# main_power.net
KiCad netlist of a schematic drawn in EAGLE
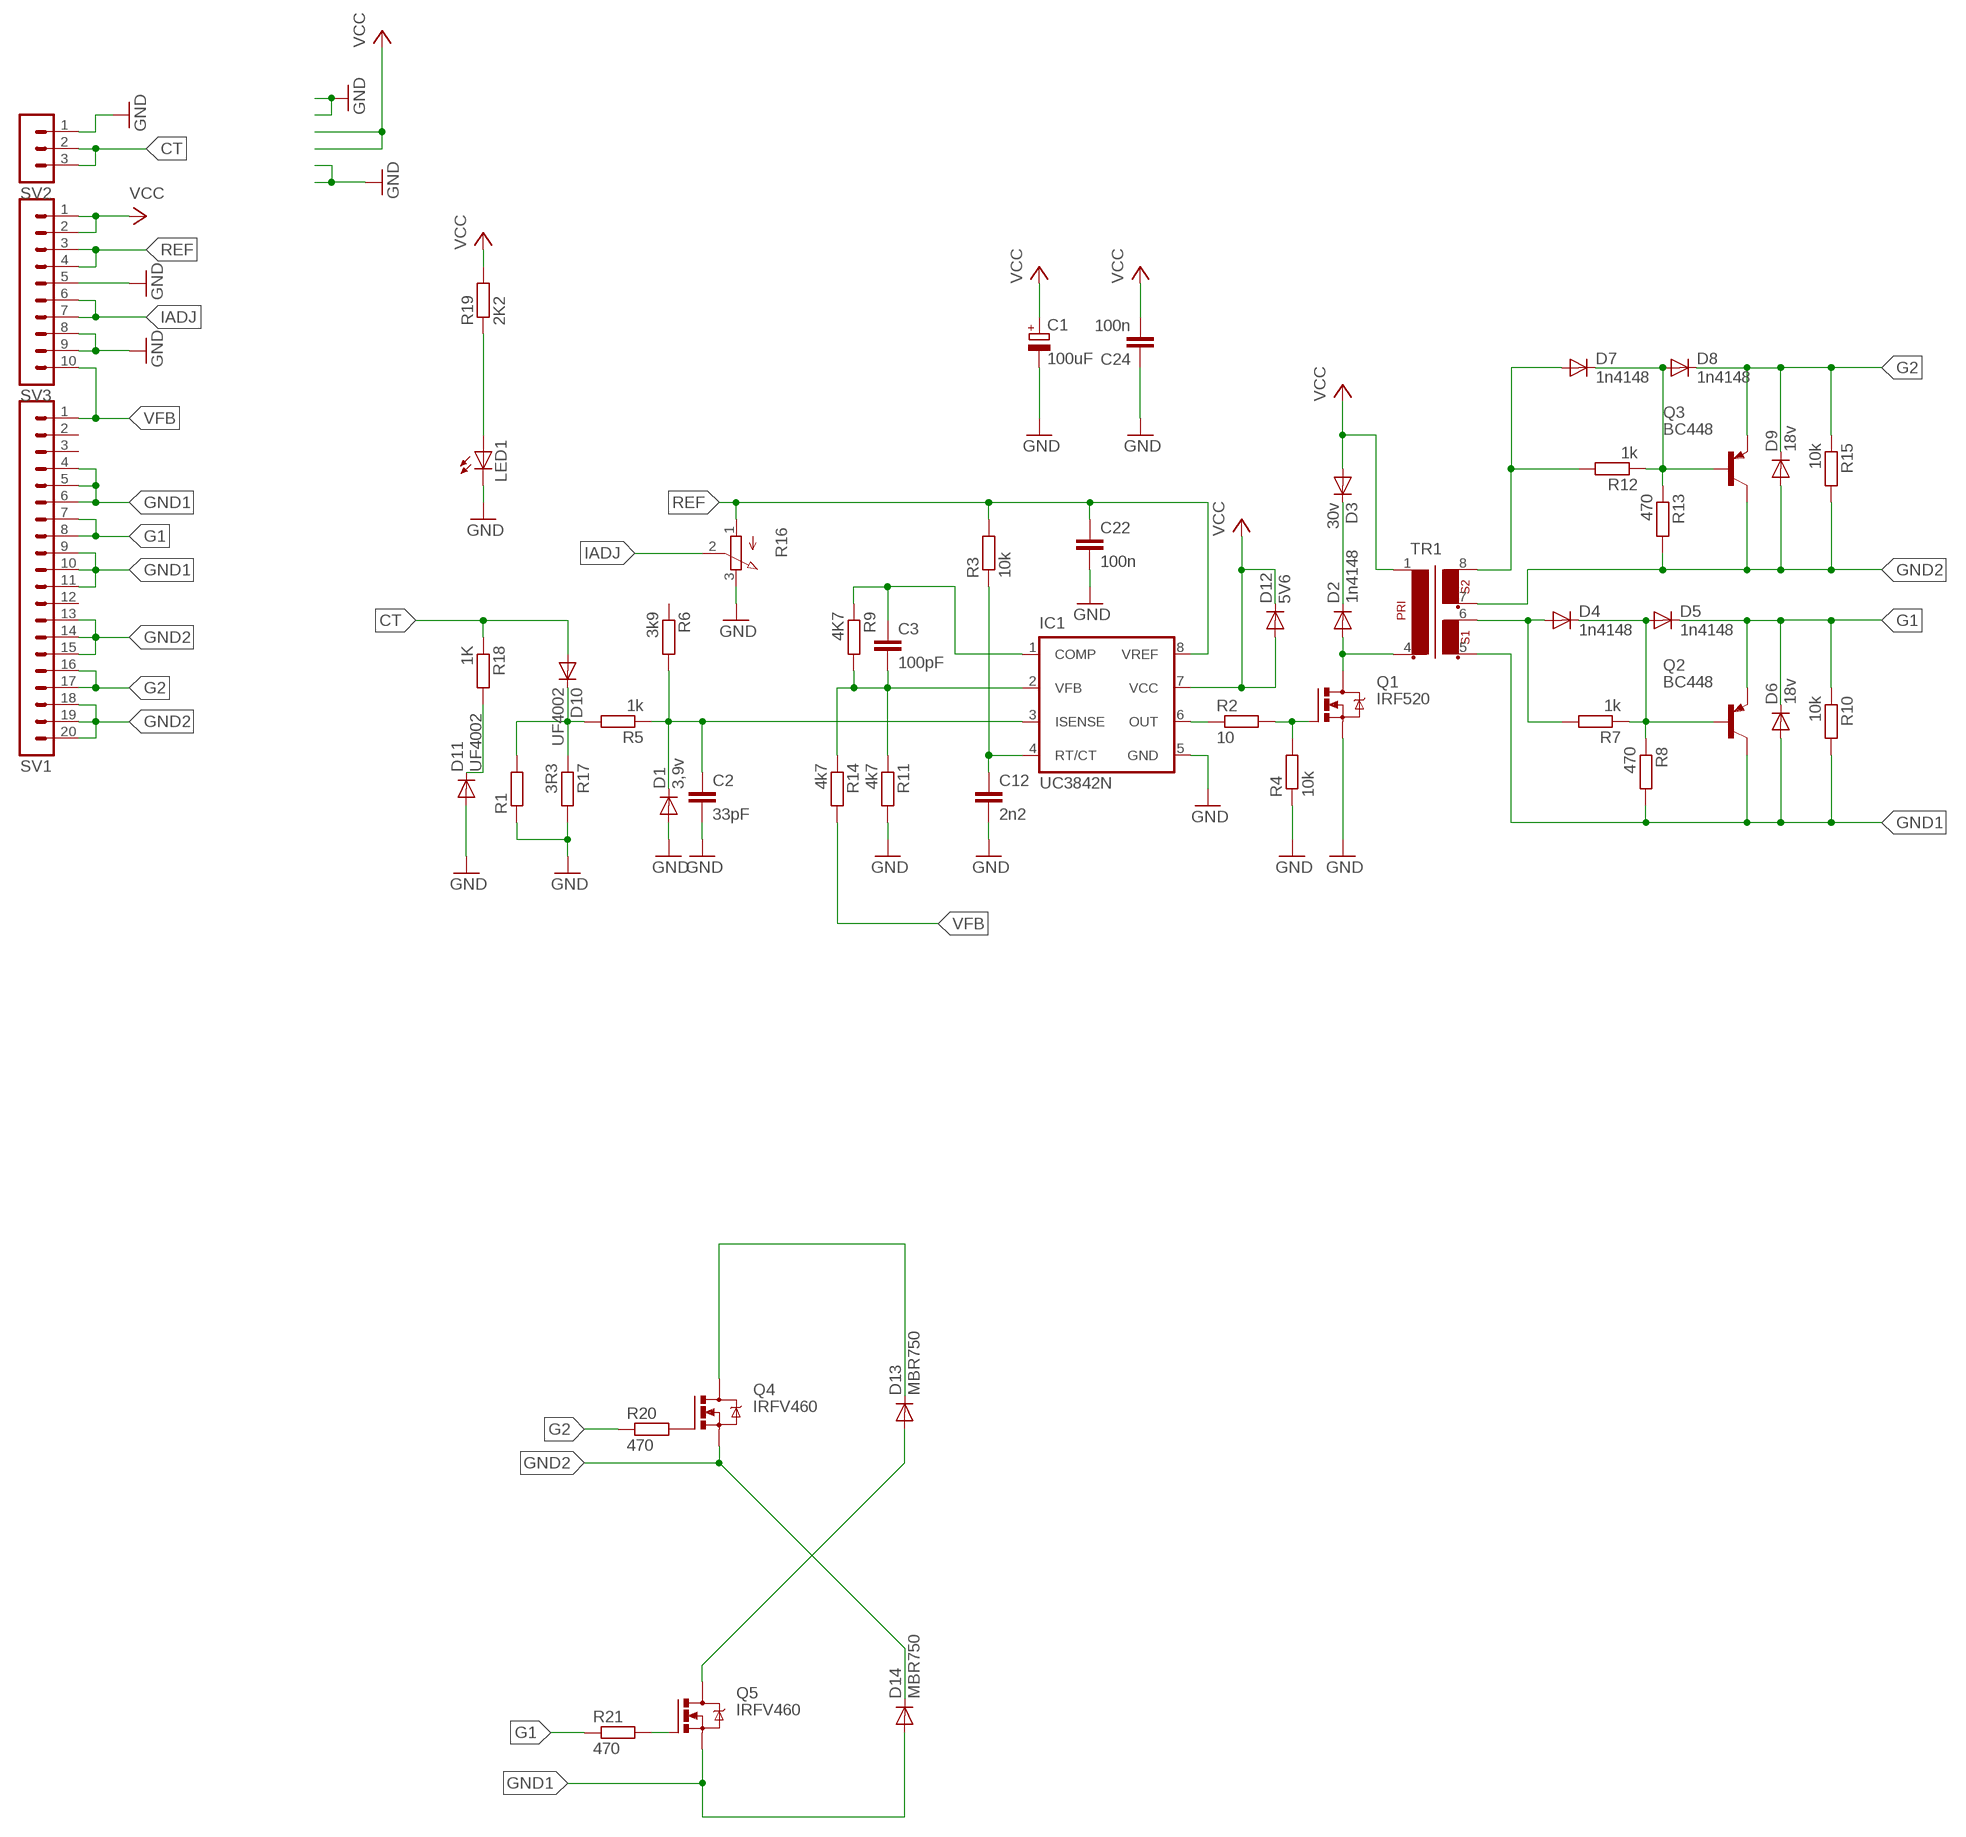
[diagram p0: schematic, sheet 1]

(export (version "E")
  (design (tool "Eeschema 10.0.6"))
  (components
    (comp (ref "C1")
      (value "100uF")
      (footprint "eagle-import:E5-6")
      (libsource (lib "eagle-import") (part "CPOL-EUE5-6"))
    )
    (comp (ref "C2")
      (value "33pF")
      (footprint "eagle-import:C050-025X075")
      (libsource (lib "eagle-import") (part "C-EU050-025X075"))
    )
    (comp (ref "C3")
      (value "100pF")
      (footprint "eagle-import:C050-025X075")
      (libsource (lib "eagle-import") (part "C-EU050-025X075"))
    )
    (comp (ref "C12")
      (value "2n2")
      (footprint "eagle-import:C050-025X075")
      (libsource (lib "eagle-import") (part "C-EU050-025X075"))
    )
    (comp (ref "C22")
      (value "100n")
      (footprint "eagle-import:C050-025X075")
      (libsource (lib "eagle-import") (part "C-EU050-025X075"))
    )
    (comp (ref "C24")
      (value "100n")
      (footprint "eagle-import:C050-025X075")
      (libsource (lib "eagle-import") (part "C-EU050-025X075"))
    )
    (comp (ref "D1")
      (value "3,9v")
      (footprint "eagle-import:DO35-10")
      (libsource (lib "eagle-import") (part "1N4446"))
    )
    (comp (ref "D2")
      (value "1n4148")
      (footprint "eagle-import:DO35-10")
      (libsource (lib "eagle-import") (part "1N4446"))
    )
    (comp (ref "D3")
      (value "30v")
      (footprint "eagle-import:DO35-10")
      (libsource (lib "eagle-import") (part "1N4446"))
    )
    (comp (ref "D4")
      (value "1n4148")
      (footprint "eagle-import:DO35-10")
      (libsource (lib "eagle-import") (part "1N4446"))
    )
    (comp (ref "D5")
      (value "1n4148")
      (footprint "eagle-import:DO35-10")
      (libsource (lib "eagle-import") (part "1N4446"))
    )
    (comp (ref "D6")
      (value "18v")
      (footprint "eagle-import:DO35-10")
      (libsource (lib "eagle-import") (part "1N4446"))
    )
    (comp (ref "D7")
      (value "1n4148")
      (footprint "eagle-import:DO35-10")
      (libsource (lib "eagle-import") (part "1N4446"))
    )
    (comp (ref "D8")
      (value "1n4148")
      (footprint "eagle-import:DO35-10")
      (libsource (lib "eagle-import") (part "1N4446"))
    )
    (comp (ref "D9")
      (value "18v")
      (footprint "eagle-import:DO35-10")
      (libsource (lib "eagle-import") (part "1N4446"))
    )
    (comp (ref "D10")
      (value "UF4002")
      (footprint "eagle-import:DO35-10")
      (libsource (lib "eagle-import") (part "1N4446"))
    )
    (comp (ref "D11")
      (value "UF4002")
      (footprint "eagle-import:DO35-10")
      (libsource (lib "eagle-import") (part "1N4446"))
    )
    (comp (ref "D12")
      (value "5V6")
      (footprint "eagle-import:DO35-10")
      (libsource (lib "eagle-import") (part "1N4446"))
    )
    (comp (ref "D13")
      (value "MBR750")
      (footprint "eagle-import:TO220AC")
      (libsource (lib "eagle-import") (part "MBR750"))
    )
    (comp (ref "D14")
      (value "MBR750")
      (footprint "eagle-import:TO220AC")
      (libsource (lib "eagle-import") (part "MBR750"))
    )
    (comp (ref "IC1")
      (value "UC3842N")
      (footprint "eagle-import:DIL08")
      (libsource (lib "eagle-import") (part "UC384N2"))
    )
    (comp (ref "LED1")
      (value "LED5MM")
      (footprint "eagle-import:LED5MM")
      (libsource (lib "eagle-import") (part "LED5MM"))
    )
    (comp (ref "Q1")
      (value "IRF520")
      (footprint "eagle-import:TO220BV")
      (libsource (lib "eagle-import") (part "IRF520"))
    )
    (comp (ref "Q2")
      (value "BC448")
      (footprint "eagle-import:TO92-EBC")
      (libsource (lib "eagle-import") (part "BC448"))
    )
    (comp (ref "Q3")
      (value "BC448")
      (footprint "eagle-import:TO92-EBC")
      (libsource (lib "eagle-import") (part "BC448"))
    )
    (comp (ref "Q4")
      (value "IRFV460")
      (footprint "eagle-import:TO258AA")
      (libsource (lib "eagle-import") (part "IRFV460"))
    )
    (comp (ref "Q5")
      (value "IRFV460")
      (footprint "eagle-import:TO258AA")
      (libsource (lib "eagle-import") (part "IRFV460"))
    )
    (comp (ref "R1")
      (value "R-EU_0411/12")
      (footprint "eagle-import:0411_12")
      (libsource (lib "eagle-import") (part "R-EU_0411/12"))
    )
    (comp (ref "R2")
      (value "10")
      (footprint "eagle-import:0207_10")
      (libsource (lib "eagle-import") (part "R-EU_0207/10"))
    )
    (comp (ref "R3")
      (value "10k")
      (footprint "eagle-import:0207_10")
      (libsource (lib "eagle-import") (part "R-EU_0207/10"))
    )
    (comp (ref "R4")
      (value "10k")
      (footprint "eagle-import:0207_10")
      (libsource (lib "eagle-import") (part "R-EU_0207/10"))
    )
    (comp (ref "R5")
      (value "1k")
      (footprint "eagle-import:0207_10")
      (libsource (lib "eagle-import") (part "R-EU_0207/10"))
    )
    (comp (ref "R6")
      (value "3k9")
      (footprint "eagle-import:0207_10")
      (libsource (lib "eagle-import") (part "R-EU_0207/10"))
    )
    (comp (ref "R7")
      (value "1k")
      (footprint "eagle-import:0207_10")
      (libsource (lib "eagle-import") (part "R-EU_0207/10"))
    )
    (comp (ref "R8")
      (value "470")
      (footprint "eagle-import:0207_10")
      (libsource (lib "eagle-import") (part "R-EU_0207/10"))
    )
    (comp (ref "R9")
      (value "4K7")
      (footprint "eagle-import:0207_10")
      (libsource (lib "eagle-import") (part "R-EU_0207/10"))
    )
    (comp (ref "R10")
      (value "10k")
      (footprint "eagle-import:0207_10")
      (libsource (lib "eagle-import") (part "R-EU_0207/10"))
    )
    (comp (ref "R11")
      (value "4k7")
      (footprint "eagle-import:0207_10")
      (libsource (lib "eagle-import") (part "R-EU_0207/10"))
    )
    (comp (ref "R12")
      (value "1k")
      (footprint "eagle-import:0207_10")
      (libsource (lib "eagle-import") (part "R-EU_0207/10"))
    )
    (comp (ref "R13")
      (value "470")
      (footprint "eagle-import:0207_10")
      (libsource (lib "eagle-import") (part "R-EU_0207/10"))
    )
    (comp (ref "R14")
      (value "4k7")
      (footprint "eagle-import:0207_10")
      (libsource (lib "eagle-import") (part "R-EU_0207/10"))
    )
    (comp (ref "R15")
      (value "10k")
      (footprint "eagle-import:0207_10")
      (libsource (lib "eagle-import") (part "R-EU_0207/10"))
    )
    (comp (ref "R16")
      (value "3RP/1610N")
      (footprint "eagle-import:3RP_1610N")
      (libsource (lib "eagle-import") (part "3RP/1610N"))
    )
    (comp (ref "R17")
      (value "3R3")
      (footprint "eagle-import:0207_10")
      (libsource (lib "eagle-import") (part "R-EU_0207/10"))
    )
    (comp (ref "R18")
      (value "1K")
      (footprint "eagle-import:0207_10")
      (libsource (lib "eagle-import") (part "R-EU_0207/10"))
    )
    (comp (ref "R19")
      (value "2K2")
      (footprint "eagle-import:0207_10")
      (libsource (lib "eagle-import") (part "R-EU_0207/10"))
    )
    (comp (ref "R20")
      (value "470")
      (footprint "eagle-import:0207_10")
      (libsource (lib "eagle-import") (part "R-EU_0207/10"))
    )
    (comp (ref "R21")
      (value "470")
      (footprint "eagle-import:0207_10")
      (libsource (lib "eagle-import") (part "R-EU_0207/10"))
    )
    (comp (ref "SV1")
      (value "MA20-1")
      (footprint "eagle-import:MA20-1")
      (libsource (lib "eagle-import") (part "MA20-1"))
    )
    (comp (ref "SV2")
      (value "MA03-1")
      (footprint "eagle-import:MA03-1")
      (libsource (lib "eagle-import") (part "MA03-1"))
    )
    (comp (ref "SV3")
      (value "MA10-1")
      (footprint "eagle-import:MA10-1")
      (libsource (lib "eagle-import") (part "MA10-1"))
    )
    (comp (ref "TR1")
      (value "EE20-2")
      (footprint "eagle-import:EE20-2")
      (libsource (lib "eagle-import") (part "EE20-2"))
    )
  )
  (nets
    (net (code "1") (name "CT") (class "Default")
      (node (ref "D10") (pin "A") (pinfunction "A_A") (pintype "passive"))
      (node (ref "R18") (pin "1") (pinfunction "1_1") (pintype "passive"))
      (node (ref "SV2") (pin "2") (pinfunction "2_2") (pintype "passive"))
      (node (ref "SV2") (pin "3") (pinfunction "3_3") (pintype "passive"))
    )
    (net (code "2") (name "G1") (class "Default")
      (node (ref "D5") (pin "C") (pinfunction "C_C") (pintype "passive"))
      (node (ref "D6") (pin "C") (pinfunction "C_C") (pintype "passive"))
      (node (ref "Q2") (pin "E") (pinfunction "E_E") (pintype "passive"))
      (node (ref "R10") (pin "1") (pinfunction "1_1") (pintype "passive"))
      (node (ref "R21") (pin "1") (pinfunction "1_1") (pintype "passive"))
      (node (ref "SV1") (pin "7") (pinfunction "7_7") (pintype "passive"))
      (node (ref "SV1") (pin "8") (pinfunction "8_8") (pintype "passive"))
    )
    (net (code "3") (name "G2") (class "Default")
      (node (ref "D8") (pin "C") (pinfunction "C_C") (pintype "passive"))
      (node (ref "D9") (pin "C") (pinfunction "C_C") (pintype "passive"))
      (node (ref "Q3") (pin "E") (pinfunction "E_E") (pintype "passive"))
      (node (ref "R15") (pin "1") (pinfunction "1_1") (pintype "passive"))
      (node (ref "R20") (pin "1") (pinfunction "1_1") (pintype "passive"))
      (node (ref "SV1") (pin "16") (pinfunction "16_16") (pintype "passive"))
      (node (ref "SV1") (pin "17") (pinfunction "17_17") (pintype "passive"))
    )
    (net (code "4") (name "GND") (class "Default")
      (node (ref "C1") (pin "-") (pinfunction "-_-") (pintype "passive"))
      (node (ref "C12") (pin "2") (pinfunction "2_2") (pintype "passive"))
      (node (ref "C2") (pin "2") (pinfunction "2_2") (pintype "passive"))
      (node (ref "C22") (pin "2") (pinfunction "2_2") (pintype "passive"))
      (node (ref "C24") (pin "1") (pinfunction "1_1") (pintype "passive"))
      (node (ref "D1") (pin "A") (pinfunction "A_A") (pintype "passive"))
      (node (ref "D11") (pin "A") (pinfunction "A_A") (pintype "passive"))
      (node (ref "IC1") (pin "5") (pinfunction "GND_5") (pintype "power_in"))
      (node (ref "LED1") (pin "K") (pinfunction "C_K") (pintype "passive"))
      (node (ref "Q1") (pin "S") (pinfunction "S_S") (pintype "passive"))
      (node (ref "R1") (pin "1") (pinfunction "1_1") (pintype "passive"))
      (node (ref "R11") (pin "2") (pinfunction "2_2") (pintype "passive"))
      (node (ref "R16") (pin "3") (pinfunction "E_3") (pintype "passive"))
      (node (ref "R17") (pin "2") (pinfunction "2_2") (pintype "passive"))
      (node (ref "R4") (pin "1") (pinfunction "1_1") (pintype "passive"))
      (node (ref "SV2") (pin "1") (pinfunction "1_1") (pintype "passive"))
      (node (ref "SV3") (pin "5") (pinfunction "5_5") (pintype "passive"))
      (node (ref "SV3") (pin "8") (pinfunction "8_8") (pintype "passive"))
      (node (ref "SV3") (pin "9") (pinfunction "9_9") (pintype "passive"))
    )
    (net (code "5") (name "GND1") (class "Default")
      (node (ref "D14") (pin "A") (pinfunction "A_A") (pintype "passive"))
      (node (ref "D6") (pin "A") (pinfunction "A_A") (pintype "passive"))
      (node (ref "Q2") (pin "C") (pinfunction "C_C") (pintype "passive"))
      (node (ref "Q5") (pin "2-S") (pinfunction "S_2-S") (pintype "passive"))
      (node (ref "R10") (pin "2") (pinfunction "2_2") (pintype "passive"))
      (node (ref "R8") (pin "2") (pinfunction "2_2") (pintype "passive"))
      (node (ref "SV1") (pin "10") (pinfunction "10_10") (pintype "passive"))
      (node (ref "SV1") (pin "11") (pinfunction "11_11") (pintype "passive"))
      (node (ref "SV1") (pin "4") (pinfunction "4_4") (pintype "passive"))
      (node (ref "SV1") (pin "5") (pinfunction "5_5") (pintype "passive"))
      (node (ref "SV1") (pin "6") (pinfunction "6_6") (pintype "passive"))
      (node (ref "SV1") (pin "9") (pinfunction "9_9") (pintype "passive"))
      (node (ref "TR1") (pin "5") (pinfunction "3_5") (pintype "passive"))
    )
    (net (code "6") (name "GND2") (class "Default")
      (node (ref "D14") (pin "C") (pinfunction "C_C") (pintype "passive"))
      (node (ref "D9") (pin "A") (pinfunction "A_A") (pintype "passive"))
      (node (ref "Q3") (pin "C") (pinfunction "C_C") (pintype "passive"))
      (node (ref "Q4") (pin "2-S") (pinfunction "S_2-S") (pintype "passive"))
      (node (ref "R13") (pin "2") (pinfunction "2_2") (pintype "passive"))
      (node (ref "R15") (pin "2") (pinfunction "2_2") (pintype "passive"))
      (node (ref "SV1") (pin "13") (pinfunction "13_13") (pintype "passive"))
      (node (ref "SV1") (pin "14") (pinfunction "14_14") (pintype "passive"))
      (node (ref "SV1") (pin "15") (pinfunction "15_15") (pintype "passive"))
      (node (ref "SV1") (pin "18") (pinfunction "18_18") (pintype "passive"))
      (node (ref "SV1") (pin "19") (pinfunction "19_19") (pintype "passive"))
      (node (ref "SV1") (pin "20") (pinfunction "20_20") (pintype "passive"))
      (node (ref "TR1") (pin "7") (pinfunction "5_7") (pintype "passive"))
    )
    (net (code "7") (name "IADJ") (class "Default")
      (node (ref "R16") (pin "2") (pinfunction "S_2") (pintype "passive"))
      (node (ref "SV3") (pin "6") (pinfunction "6_6") (pintype "passive"))
      (node (ref "SV3") (pin "7") (pinfunction "7_7") (pintype "passive"))
    )
    (net (code "8") (name "Net-(D2-PadC)") (class "Default")
      (node (ref "D2") (pin "C") (pinfunction "C_C") (pintype "passive"))
      (node (ref "D3") (pin "C") (pinfunction "C_C") (pintype "passive"))
    )
    (net (code "9") (name "Net-(D4-PadC)") (class "Default")
      (node (ref "D4") (pin "C") (pinfunction "C_C") (pintype "passive"))
      (node (ref "D5") (pin "A") (pinfunction "A_A") (pintype "passive"))
      (node (ref "Q2") (pin "B") (pinfunction "B_B") (pintype "passive"))
      (node (ref "R7") (pin "1") (pinfunction "1_1") (pintype "passive"))
      (node (ref "R8") (pin "1") (pinfunction "1_1") (pintype "passive"))
    )
    (net (code "10") (name "Net-(D7-PadC)") (class "Default")
      (node (ref "D7") (pin "C") (pinfunction "C_C") (pintype "passive"))
      (node (ref "D8") (pin "A") (pinfunction "A_A") (pintype "passive"))
      (node (ref "Q3") (pin "B") (pinfunction "B_B") (pintype "passive"))
      (node (ref "R12") (pin "1") (pinfunction "1_1") (pintype "passive"))
      (node (ref "R13") (pin "1") (pinfunction "1_1") (pintype "passive"))
    )
    (net (code "11") (name "Net-(D10-PadC)") (class "Default")
      (node (ref "D10") (pin "C") (pinfunction "C_C") (pintype "passive"))
      (node (ref "R1") (pin "2") (pinfunction "2_2") (pintype "passive"))
      (node (ref "R17") (pin "1") (pinfunction "1_1") (pintype "passive"))
      (node (ref "R5") (pin "2") (pinfunction "2_2") (pintype "passive"))
    )
    (net (code "12") (name "Net-(D11-PadC)") (class "Default")
      (node (ref "D11") (pin "C") (pinfunction "C_C") (pintype "passive"))
      (node (ref "R18") (pin "2") (pinfunction "2_2") (pintype "passive"))
    )
    (net (code "13") (name "Net-(IC1-COMP)") (class "Default")
      (node (ref "C3") (pin "1") (pinfunction "1_1") (pintype "passive"))
      (node (ref "IC1") (pin "1") (pinfunction "COMP_1") (pintype "passive"))
      (node (ref "R9") (pin "1") (pinfunction "1_1") (pintype "passive"))
    )
    (net (code "14") (name "Net-(IC1-ISENSE)") (class "Default")
      (node (ref "C2") (pin "1") (pinfunction "1_1") (pintype "passive"))
      (node (ref "D1") (pin "C") (pinfunction "C_C") (pintype "passive"))
      (node (ref "IC1") (pin "3") (pinfunction "ISENSE_3") (pintype "input"))
      (node (ref "R5") (pin "1") (pinfunction "1_1") (pintype "passive"))
      (node (ref "R6") (pin "2") (pinfunction "2_2") (pintype "passive"))
    )
    (net (code "15") (name "Net-(IC1-OUT)") (class "Default")
      (node (ref "IC1") (pin "6") (pinfunction "OUT_6") (pintype "output"))
      (node (ref "R2") (pin "1") (pinfunction "1_1") (pintype "passive"))
    )
    (net (code "16") (name "Net-(IC1-RT{slash}CT)") (class "Default")
      (node (ref "C12") (pin "1") (pinfunction "1_1") (pintype "passive"))
      (node (ref "IC1") (pin "4") (pinfunction "RT/CT_4") (pintype "passive"))
      (node (ref "R3") (pin "1") (pinfunction "1_1") (pintype "passive"))
    )
    (net (code "17") (name "Net-(IC1-VFB)") (class "Default")
      (node (ref "C3") (pin "2") (pinfunction "2_2") (pintype "passive"))
      (node (ref "IC1") (pin "2") (pinfunction "VFB_2") (pintype "input"))
      (node (ref "R11") (pin "1") (pinfunction "1_1") (pintype "passive"))
      (node (ref "R14") (pin "1") (pinfunction "1_1") (pintype "passive"))
      (node (ref "R9") (pin "2") (pinfunction "2_2") (pintype "passive"))
    )
    (net (code "18") (name "Net-(LED1-PadA)") (class "Default")
      (node (ref "LED1") (pin "A") (pinfunction "A_A") (pintype "passive"))
      (node (ref "R19") (pin "1") (pinfunction "1_1") (pintype "passive"))
    )
    (net (code "19") (name "Net-(Q1-PadG)") (class "Default")
      (node (ref "Q1") (pin "G") (pinfunction "G_G") (pintype "passive"))
      (node (ref "R2") (pin "2") (pinfunction "2_2") (pintype "passive"))
      (node (ref "R4") (pin "2") (pinfunction "2_2") (pintype "passive"))
    )
    (net (code "20") (name "Net-(Q4-D)") (class "Default")
      (node (ref "D13") (pin "C") (pinfunction "C_C") (pintype "passive"))
      (node (ref "Q4") (pin "1-D") (pinfunction "D_1-D") (pintype "passive"))
    )
    (net (code "21") (name "Net-(Q4-G)") (class "Default")
      (node (ref "Q4") (pin "3-G") (pinfunction "G_3-G") (pintype "passive"))
      (node (ref "R20") (pin "2") (pinfunction "2_2") (pintype "passive"))
    )
    (net (code "22") (name "Net-(Q5-D)") (class "Default")
      (node (ref "D13") (pin "A") (pinfunction "A_A") (pintype "passive"))
      (node (ref "Q5") (pin "1-D") (pinfunction "D_1-D") (pintype "passive"))
    )
    (net (code "23") (name "Net-(Q5-G)") (class "Default")
      (node (ref "Q5") (pin "3-G") (pinfunction "G_3-G") (pintype "passive"))
      (node (ref "R21") (pin "2") (pinfunction "2_2") (pintype "passive"))
    )
    (net (code "24") (name "Net-(TR1-2)") (class "Default")
      (node (ref "D2") (pin "A") (pinfunction "A_A") (pintype "passive"))
      (node (ref "Q1") (pin "D") (pinfunction "D_D") (pintype "passive"))
      (node (ref "TR1") (pin "4") (pinfunction "2_4") (pintype "passive"))
    )
    (net (code "25") (name "Net-(TR1-4)") (class "Default")
      (node (ref "D4") (pin "A") (pinfunction "A_A") (pintype "passive"))
      (node (ref "R7") (pin "2") (pinfunction "2_2") (pintype "passive"))
      (node (ref "TR1") (pin "6") (pinfunction "4_6") (pintype "passive"))
    )
    (net (code "26") (name "Net-(TR1-6)") (class "Default")
      (node (ref "D7") (pin "A") (pinfunction "A_A") (pintype "passive"))
      (node (ref "R12") (pin "2") (pinfunction "2_2") (pintype "passive"))
      (node (ref "TR1") (pin "8") (pinfunction "6_8") (pintype "passive"))
    )
    (net (code "27") (name "REF") (class "Default")
      (node (ref "C22") (pin "1") (pinfunction "1_1") (pintype "passive"))
      (node (ref "IC1") (pin "8") (pinfunction "VREF_8") (pintype "passive"))
      (node (ref "R16") (pin "1") (pinfunction "A_1") (pintype "passive"))
      (node (ref "R3") (pin "2") (pinfunction "2_2") (pintype "passive"))
      (node (ref "SV3") (pin "3") (pinfunction "3_3") (pintype "passive"))
      (node (ref "SV3") (pin "4") (pinfunction "4_4") (pintype "passive"))
    )
    (net (code "28") (name "VCC") (class "Default")
      (node (ref "C1") (pin "+") (pinfunction "+_+") (pintype "passive"))
      (node (ref "C24") (pin "2") (pinfunction "2_2") (pintype "passive"))
      (node (ref "D12") (pin "A") (pinfunction "A_A") (pintype "passive"))
      (node (ref "D12") (pin "C") (pinfunction "C_C") (pintype "passive"))
      (node (ref "D3") (pin "A") (pinfunction "A_A") (pintype "passive"))
      (node (ref "IC1") (pin "7") (pinfunction "VCC_7") (pintype "power_in"))
      (node (ref "R19") (pin "2") (pinfunction "2_2") (pintype "passive"))
      (node (ref "SV3") (pin "1") (pinfunction "1_1") (pintype "passive"))
      (node (ref "SV3") (pin "2") (pinfunction "2_2") (pintype "passive"))
      (node (ref "TR1") (pin "1") (pinfunction "1_1") (pintype "passive"))
    )
    (net (code "29") (name "VFB") (class "Default")
      (node (ref "R14") (pin "2") (pinfunction "2_2") (pintype "passive"))
      (node (ref "SV1") (pin "1") (pinfunction "1_1") (pintype "passive"))
      (node (ref "SV3") (pin "10") (pinfunction "10_10") (pintype "passive"))
    )
    (net (code "30") (name "unconnected-(R6-Pad1)") (class "Default")
      (node (ref "R6") (pin "1") (pinfunction "1_1") (pintype "passive"))
    )
    (net (code "31") (name "unconnected-(SV1-Pad2)") (class "Default")
      (node (ref "SV1") (pin "2") (pinfunction "2_2") (pintype "passive"))
    )
    (net (code "32") (name "unconnected-(SV1-Pad3)") (class "Default")
      (node (ref "SV1") (pin "3") (pinfunction "3_3") (pintype "passive"))
    )
    (net (code "33") (name "unconnected-(SV1-Pad12)") (class "Default")
      (node (ref "SV1") (pin "12") (pinfunction "12_12") (pintype "passive"))
    )
  )
)
